# UWB_IMU.net
KiCad netlist of a schematic drawn in Altium Designer
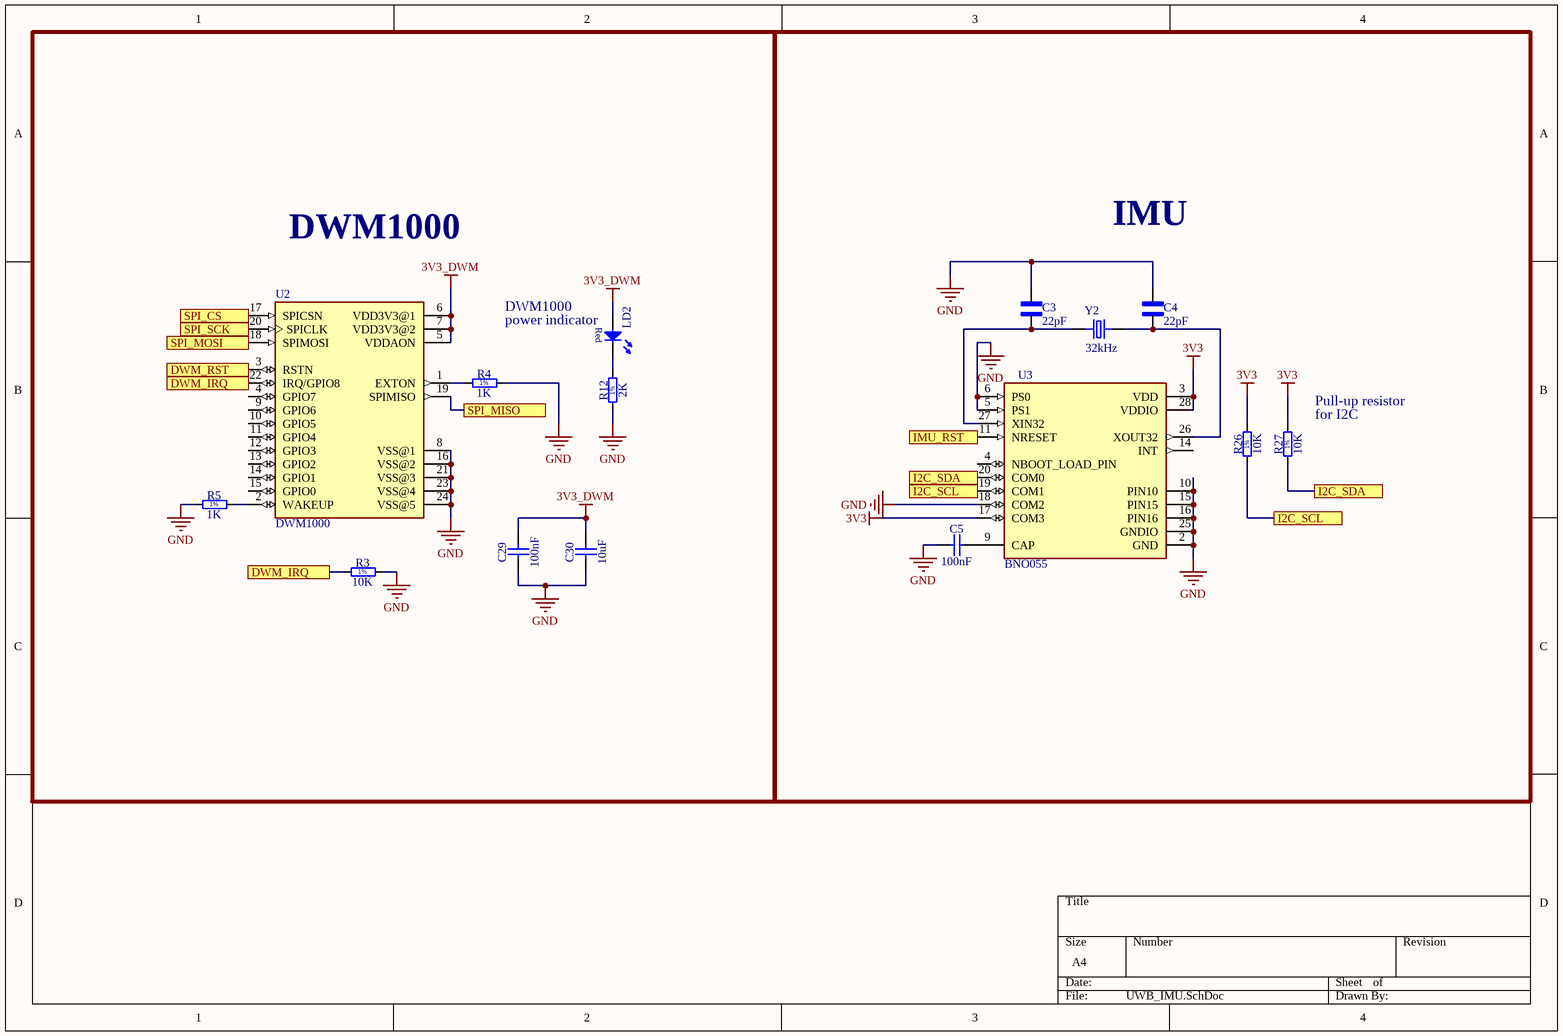
[diagram p0: UWB_IMU.SchDoc]

(export (version "E")
  (design (tool "Eeschema 10.0.6"))
  (components
    (comp (ref "C3")
      (value "22pF")
      (footprint "CAPC1005X55N")
      (description "10 pF Â±5% 50V Ceramic Capacitor C0G, NP0 0402 (1005 Metric)")
      (fields (field (name "MF") "Walsin Technology") (field (name "MP") "0402N100J500CT"))
      (libsource (lib "0402N100J500CT") (part "0402N100J500CT"))
    )
    (comp (ref "C4")
      (value "22pF")
      (footprint "CAPC1005X55N")
      (description "10 pF Â±5% 50V Ceramic Capacitor C0G, NP0 0402 (1005 Metric)")
      (fields (field (name "MF") "Walsin Technology") (field (name "MP") "0402N100J500CT"))
      (libsource (lib "0402N100J500CT") (part "0402N100J500CT"))
    )
    (comp (ref "C5")
      (value "100nF")
      (footprint "0603C")
      (description "Non-polarised capacitor")
      (libsource (lib "Universal Acq") (part "Capacitor - non polarized"))
    )
    (comp (ref "C29")
      (value "100nF")
      (footprint "0603C")
      (description "Non-polarised capacitor")
      (libsource (lib "Universal Acq") (part "Capacitor - non polarized"))
    )
    (comp (ref "C30")
      (value "10uF")
      (footprint "0603C")
      (description "Non-polarised capacitor")
      (libsource (lib "Universal Acq") (part "Capacitor - non polarized"))
    )
    (comp (ref "LD2")
      (value "~")
      (footprint "0603 LED")
      (description "LED Red 1C 2A")
      (libsource (lib "Universal Acq") (part "LED Red 1C 2A"))
    )
    (comp (ref "R3")
      (value "10K")
      (footprint "0603R")
      (description "Resistor - 1%")
      (libsource (lib "Universal Acq") (part "Resistor - 1%_1"))
    )
    (comp (ref "R4")
      (value "1K")
      (footprint "0603R")
      (description "Resistor - 1%")
      (libsource (lib "Universal Acq") (part "Resistor - 1%_1"))
    )
    (comp (ref "R5")
      (value "1K")
      (footprint "0603R")
      (description "Resistor - 1%")
      (libsource (lib "Universal Acq") (part "Resistor - 1%_1"))
    )
    (comp (ref "R12")
      (value "2K")
      (footprint "0603R")
      (description "Resistor - 1%")
      (libsource (lib "Universal Acq") (part "Resistor - 1%_1"))
    )
    (comp (ref "R26")
      (value "10K")
      (footprint "0603R")
      (description "Resistor - 1%")
      (libsource (lib "Universal Acq") (part "Resistor - 1%_1"))
    )
    (comp (ref "R27")
      (value "10K")
      (footprint "0603R")
      (description "Resistor - 1%")
      (libsource (lib "Universal Acq") (part "Resistor - 1%_1"))
    )
    (comp (ref "U2")
      (value "DWM1000")
      (footprint "XCVR_DWM1000")
      (description "802.15.4 IR-UWB Transceiver Module 3.5GHz ~ 6.5GHz Integrated, Chip Surface Mount")
      (fields (field (name "MF") "Decawave Limited"))
      (libsource (lib "DWM1000") (part "DWM1000"))
    )
    (comp (ref "U3")
      (value "BNO055")
      (footprint "LGA28R50P4X10_380X520X100")
      (description "BNO055 9-axis Absolute Orientation Sensor ( SiP ) w/Sensors and Sensor Fusion")
      (libsource (lib "BNO055") (part "BNO055"))
    )
    (comp (ref "Y2")
      (value "32kHz")
      (footprint "XTAL_ECS-.327-6-34RR-TR")
      (description "32.768kHz 20ppm Crystal 6pF 20 kOhm -40C ~ 85C Surface Mount 2-SMD, No Lead 3.2 x 1.5")
      (fields (field (name "MF") "ECS Inc.") (field (name "MP") "ECS-.327-6-34RR-TR"))
      (libsource (lib "ECS-.327-6-34RR-TR") (part "ECS-.327-6-34RR-TR"))
    )
  )
  (nets
    (net (code "1") (name "/DWM_IRQ") (class "Default")
      (node (ref "R3") (pin "1") (pinfunction "1_1") (pintype "passive"))
      (node (ref "U2") (pin "22") (pinfunction "IRQ/GPIO8_22") (pintype "bidirectional"))
    )
    (net (code "2") (name "/DWM_RST") (class "Default")
      (node (ref "U2") (pin "3") (pinfunction "RSTN_3") (pintype "bidirectional"))
    )
    (net (code "3") (name "/I2C_SCL") (class "Default")
      (node (ref "R26") (pin "1") (pinfunction "1_1") (pintype "passive"))
      (node (ref "U3") (pin "19") (pinfunction "COM1_19") (pintype "bidirectional"))
    )
    (net (code "4") (name "/I2C_SDA") (class "Default")
      (node (ref "R27") (pin "1") (pinfunction "1_1") (pintype "passive"))
      (node (ref "U3") (pin "20") (pinfunction "COM0_20") (pintype "bidirectional"))
    )
    (net (code "5") (name "/IMU_RST") (class "Default")
      (node (ref "U3") (pin "11") (pinfunction "NRESET_11") (pintype "input"))
    )
    (net (code "6") (name "/SPI_CS") (class "Default")
      (node (ref "U2") (pin "17") (pinfunction "SPICSN_17") (pintype "input"))
    )
    (net (code "7") (name "/SPI_MISO") (class "Default")
      (node (ref "U2") (pin "19") (pinfunction "SPIMISO_19") (pintype "output"))
    )
    (net (code "8") (name "/SPI_MOSI") (class "Default")
      (node (ref "U2") (pin "18") (pinfunction "SPIMOSI_18") (pintype "input"))
    )
    (net (code "9") (name "/SPI_SCK") (class "Default")
      (node (ref "U2") (pin "20") (pinfunction "SPICLK_20") (pintype "input"))
    )
    (net (code "10") (name "3V3") (class "Default")
      (node (ref "R26") (pin "2") (pinfunction "2_2") (pintype "passive"))
      (node (ref "R27") (pin "2") (pinfunction "2_2") (pintype "passive"))
      (node (ref "U3") (pin "17") (pinfunction "COM3_17") (pintype "bidirectional"))
      (node (ref "U3") (pin "28") (pinfunction "VDDIO_28") (pintype "power_in"))
      (node (ref "U3") (pin "3") (pinfunction "VDD_3") (pintype "power_in"))
    )
    (net (code "11") (name "3V3_DWM") (class "Default")
      (node (ref "C29") (pin "2") (pinfunction "2_2") (pintype "passive"))
      (node (ref "C30") (pin "2") (pinfunction "2_2") (pintype "passive"))
      (node (ref "LD2") (pin "2") (pinfunction "A_2") (pintype "passive"))
      (node (ref "U2") (pin "5") (pinfunction "VDDAON_5") (pintype "power_in"))
      (node (ref "U2") (pin "6") (pinfunction "VDD3V3@1_6") (pintype "power_in"))
      (node (ref "U2") (pin "7") (pinfunction "VDD3V3@2_7") (pintype "power_in"))
    )
    (net (code "12") (name "GND") (class "Default")
      (node (ref "C29") (pin "1") (pinfunction "1_1") (pintype "passive"))
      (node (ref "C3") (pin "2") (pinfunction "2_2") (pintype "passive"))
      (node (ref "C30") (pin "1") (pinfunction "1_1") (pintype "passive"))
      (node (ref "C4") (pin "2") (pinfunction "2_2") (pintype "passive"))
      (node (ref "C5") (pin "1") (pinfunction "1_1") (pintype "passive"))
      (node (ref "R12") (pin "1") (pinfunction "1_1") (pintype "passive"))
      (node (ref "R3") (pin "2") (pinfunction "2_2") (pintype "passive"))
      (node (ref "R4") (pin "2") (pinfunction "2_2") (pintype "passive"))
      (node (ref "R5") (pin "1") (pinfunction "1_1") (pintype "passive"))
      (node (ref "U2") (pin "16") (pinfunction "VSS@2_16") (pintype "power_in"))
      (node (ref "U2") (pin "21") (pinfunction "VSS@3_21") (pintype "power_in"))
      (node (ref "U2") (pin "23") (pinfunction "VSS@4_23") (pintype "power_in"))
      (node (ref "U2") (pin "24") (pinfunction "VSS@5_24") (pintype "power_in"))
      (node (ref "U2") (pin "8") (pinfunction "VSS@1_8") (pintype "power_in"))
      (node (ref "U3") (pin "10") (pinfunction "PIN10_10") (pintype "power_in"))
      (node (ref "U3") (pin "15") (pinfunction "PIN15_15") (pintype "power_in"))
      (node (ref "U3") (pin "16") (pinfunction "PIN16_16") (pintype "power_in"))
      (node (ref "U3") (pin "18") (pinfunction "COM2_18") (pintype "bidirectional"))
      (node (ref "U3") (pin "2") (pinfunction "GND_2") (pintype "power_in"))
      (node (ref "U3") (pin "25") (pinfunction "GNDIO_25") (pintype "power_in"))
      (node (ref "U3") (pin "5") (pinfunction "PS1_5") (pintype "input"))
      (node (ref "U3") (pin "6") (pinfunction "PS0_6") (pintype "input"))
    )
    (net (code "13") (name "Net-(LD2-C)") (class "Default")
      (node (ref "LD2") (pin "1") (pinfunction "C_1") (pintype "passive"))
      (node (ref "R12") (pin "2") (pinfunction "2_2") (pintype "passive"))
    )
    (net (code "14") (name "Net-(U2-EXTON)") (class "Default")
      (node (ref "R4") (pin "1") (pinfunction "1_1") (pintype "passive"))
      (node (ref "U2") (pin "1") (pinfunction "EXTON_1") (pintype "output"))
    )
    (net (code "15") (name "Net-(U2-WAKEUP)") (class "Default")
      (node (ref "R5") (pin "2") (pinfunction "2_2") (pintype "passive"))
      (node (ref "U2") (pin "2") (pinfunction "WAKEUP_2") (pintype "bidirectional"))
    )
    (net (code "16") (name "Net-(U3-CAP)") (class "Default")
      (node (ref "C5") (pin "2") (pinfunction "2_2") (pintype "passive"))
      (node (ref "U3") (pin "9") (pinfunction "CAP_9") (pintype "passive"))
    )
    (net (code "17") (name "Net-(U3-XIN32)") (class "Default")
      (node (ref "C3") (pin "1") (pinfunction "1_1") (pintype "passive"))
      (node (ref "U3") (pin "27") (pinfunction "XIN32_27") (pintype "input"))
      (node (ref "Y2") (pin "1") (pinfunction "I/O_1") (pintype "passive"))
    )
    (net (code "18") (name "Net-(U3-XOUT32)") (class "Default")
      (node (ref "C4") (pin "1") (pinfunction "1_1") (pintype "passive"))
      (node (ref "U3") (pin "26") (pinfunction "XOUT32_26") (pintype "output"))
      (node (ref "Y2") (pin "2") (pinfunction "O/I_2") (pintype "passive"))
    )
    (net (code "19") (name "unconnected-(U2-GPIO0-Pad15)") (class "Default")
      (node (ref "U2") (pin "15") (pinfunction "GPIO0_15") (pintype "bidirectional"))
    )
    (net (code "20") (name "unconnected-(U2-GPIO1-Pad14)") (class "Default")
      (node (ref "U2") (pin "14") (pinfunction "GPIO1_14") (pintype "bidirectional"))
    )
    (net (code "21") (name "unconnected-(U2-GPIO2-Pad13)") (class "Default")
      (node (ref "U2") (pin "13") (pinfunction "GPIO2_13") (pintype "bidirectional"))
    )
    (net (code "22") (name "unconnected-(U2-GPIO3-Pad12)") (class "Default")
      (node (ref "U2") (pin "12") (pinfunction "GPIO3_12") (pintype "bidirectional"))
    )
    (net (code "23") (name "unconnected-(U2-GPIO4-Pad11)") (class "Default")
      (node (ref "U2") (pin "11") (pinfunction "GPIO4_11") (pintype "bidirectional"))
    )
    (net (code "24") (name "unconnected-(U2-GPIO5-Pad10)") (class "Default")
      (node (ref "U2") (pin "10") (pinfunction "GPIO5_10") (pintype "bidirectional"))
    )
    (net (code "25") (name "unconnected-(U2-GPIO6-Pad9)") (class "Default")
      (node (ref "U2") (pin "9") (pinfunction "GPIO6_9") (pintype "bidirectional"))
    )
    (net (code "26") (name "unconnected-(U2-GPIO7-Pad4)") (class "Default")
      (node (ref "U2") (pin "4") (pinfunction "GPIO7_4") (pintype "bidirectional"))
    )
    (net (code "27") (name "unconnected-(U3-INT-Pad14)") (class "Default")
      (node (ref "U3") (pin "14") (pinfunction "INT_14") (pintype "output"))
    )
    (net (code "28") (name "unconnected-(U3-NBOOT_LOAD_PIN-Pad4)") (class "Default")
      (node (ref "U3") (pin "4") (pinfunction "NBOOT_LOAD_PIN_4") (pintype "bidirectional"))
    )
  )
)
